# connector.net
KiCad netlist of a schematic drawn in Altium Designer
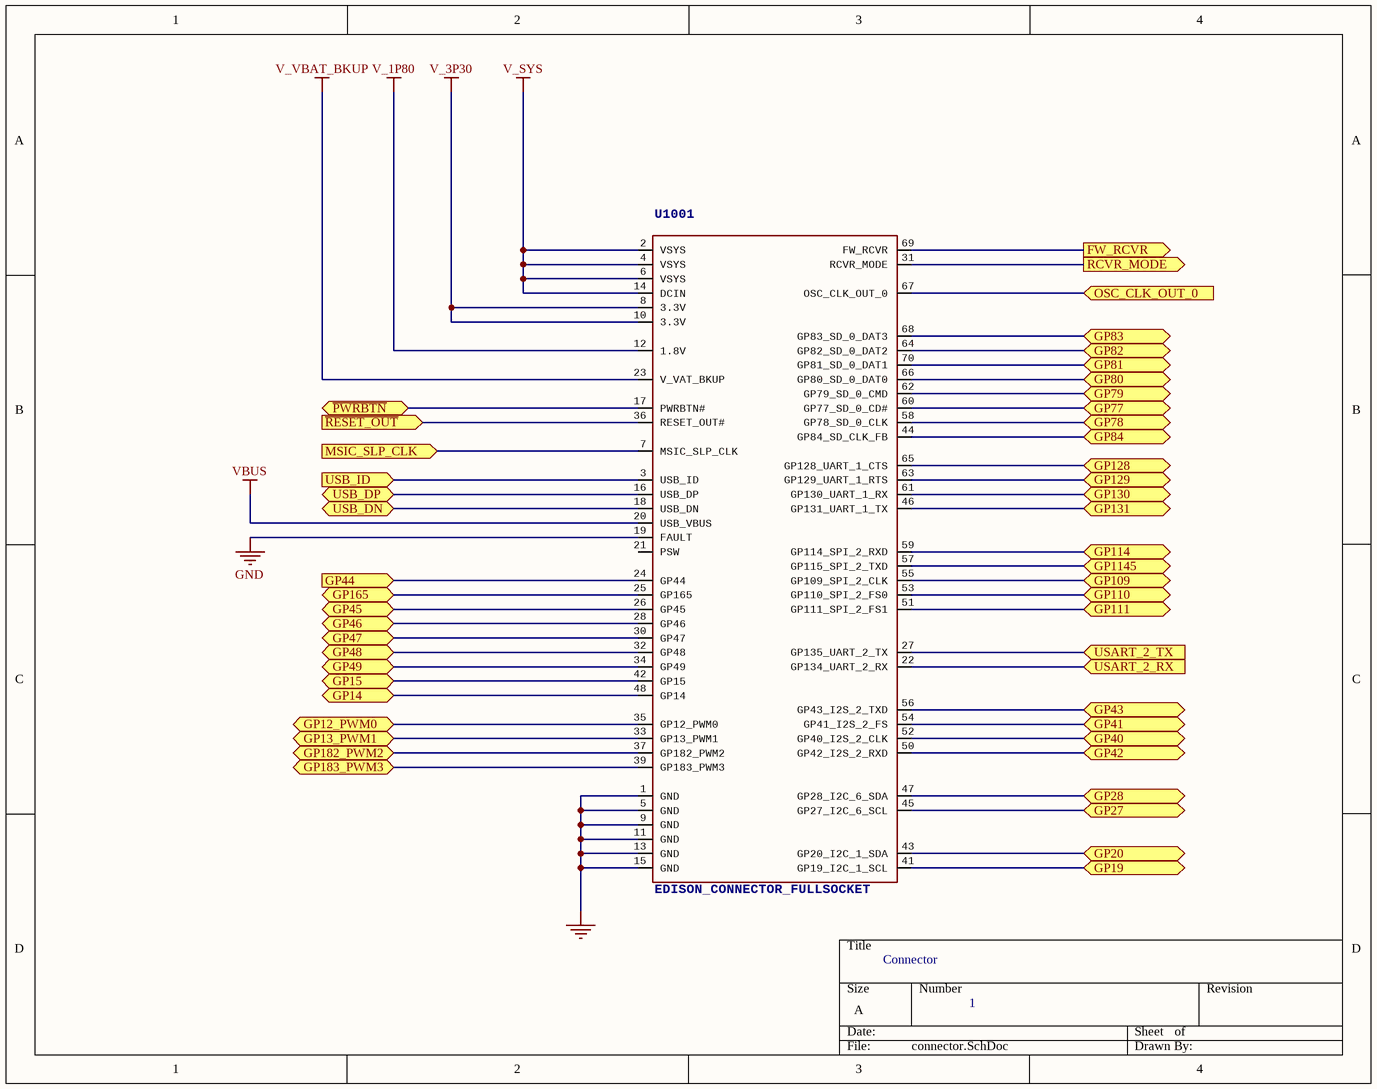
[diagram p0: connector.SchDoc]

(export (version "E")
  (design (tool "Eeschema 10.0.6"))
  (components
    (comp (ref "U1001")
      (value "EDISON_CONNECTOR_FULLSOCKET")
      (footprint "EDISON_DAUGHTER_TOP")
      (libsource (lib "Edison") (part "EDISON_CONNECTOR_FULLSOCKET"))
    )
  )
  (nets
    (net (code "1") (name "/FW_RCVR") (class "Default")
      (node (ref "U1001") (pin "69") (pinfunction "FW_RCVR_69") (pintype "passive"))
    )
    (net (code "2") (name "/GP12_PWM0") (class "Default")
      (node (ref "U1001") (pin "35") (pinfunction "GP12_PWM0_35") (pintype "passive"))
    )
    (net (code "3") (name "/GP13_PWM1") (class "Default")
      (node (ref "U1001") (pin "33") (pinfunction "GP13_PWM1_33") (pintype "passive"))
    )
    (net (code "4") (name "/GP14") (class "Default")
      (node (ref "U1001") (pin "48") (pinfunction "GP14_48") (pintype "passive"))
    )
    (net (code "5") (name "/GP15") (class "Default")
      (node (ref "U1001") (pin "42") (pinfunction "GP15_42") (pintype "passive"))
    )
    (net (code "6") (name "/GP19") (class "Default")
      (node (ref "U1001") (pin "41") (pinfunction "GP19_I2C_1_SCL_41") (pintype "passive"))
    )
    (net (code "7") (name "/GP20") (class "Default")
      (node (ref "U1001") (pin "43") (pinfunction "GP20_I2C_1_SDA_43") (pintype "passive"))
    )
    (net (code "8") (name "/GP27") (class "Default")
      (node (ref "U1001") (pin "45") (pinfunction "GP27_I2C_6_SCL_45") (pintype "passive"))
    )
    (net (code "9") (name "/GP28") (class "Default")
      (node (ref "U1001") (pin "47") (pinfunction "GP28_I2C_6_SDA_47") (pintype "passive"))
    )
    (net (code "10") (name "/GP40") (class "Default")
      (node (ref "U1001") (pin "52") (pinfunction "GP40_I2S_2_CLK_52") (pintype "passive"))
    )
    (net (code "11") (name "/GP41") (class "Default")
      (node (ref "U1001") (pin "54") (pinfunction "GP41_I2S_2_FS_54") (pintype "passive"))
    )
    (net (code "12") (name "/GP42") (class "Default")
      (node (ref "U1001") (pin "50") (pinfunction "GP42_I2S_2_RXD_50") (pintype "passive"))
    )
    (net (code "13") (name "/GP43") (class "Default")
      (node (ref "U1001") (pin "56") (pinfunction "GP43_I2S_2_TXD_56") (pintype "passive"))
    )
    (net (code "14") (name "/GP44") (class "Default")
      (node (ref "U1001") (pin "24") (pinfunction "GP44_24") (pintype "passive"))
    )
    (net (code "15") (name "/GP45") (class "Default")
      (node (ref "U1001") (pin "26") (pinfunction "GP45_26") (pintype "passive"))
    )
    (net (code "16") (name "/GP46") (class "Default")
      (node (ref "U1001") (pin "28") (pinfunction "GP46_28") (pintype "passive"))
    )
    (net (code "17") (name "/GP47") (class "Default")
      (node (ref "U1001") (pin "30") (pinfunction "GP47_30") (pintype "passive"))
    )
    (net (code "18") (name "/GP48") (class "Default")
      (node (ref "U1001") (pin "32") (pinfunction "GP48_32") (pintype "passive"))
    )
    (net (code "19") (name "/GP49") (class "Default")
      (node (ref "U1001") (pin "34") (pinfunction "GP49_34") (pintype "passive"))
    )
    (net (code "20") (name "/GP77") (class "Default")
      (node (ref "U1001") (pin "60") (pinfunction "GP77_SD_0_CD#_60") (pintype "passive"))
    )
    (net (code "21") (name "/GP78") (class "Default")
      (node (ref "U1001") (pin "58") (pinfunction "GP78_SD_0_CLK_58") (pintype "passive"))
    )
    (net (code "22") (name "/GP79") (class "Default")
      (node (ref "U1001") (pin "62") (pinfunction "GP79_SD_0_CMD_62") (pintype "passive"))
    )
    (net (code "23") (name "/GP80") (class "Default")
      (node (ref "U1001") (pin "66") (pinfunction "GP80_SD_0_DAT0_66") (pintype "passive"))
    )
    (net (code "24") (name "/GP81") (class "Default")
      (node (ref "U1001") (pin "70") (pinfunction "GP81_SD_0_DAT1_70") (pintype "passive"))
    )
    (net (code "25") (name "/GP82") (class "Default")
      (node (ref "U1001") (pin "64") (pinfunction "GP82_SD_0_DAT2_64") (pintype "passive"))
    )
    (net (code "26") (name "/GP83") (class "Default")
      (node (ref "U1001") (pin "68") (pinfunction "GP83_SD_0_DAT3_68") (pintype "passive"))
    )
    (net (code "27") (name "/GP84") (class "Default")
      (node (ref "U1001") (pin "44") (pinfunction "GP84_SD_CLK_FB_44") (pintype "passive"))
    )
    (net (code "28") (name "/GP109") (class "Default")
      (node (ref "U1001") (pin "55") (pinfunction "GP109_SPI_2_CLK_55") (pintype "passive"))
    )
    (net (code "29") (name "/GP110") (class "Default")
      (node (ref "U1001") (pin "53") (pinfunction "GP110_SPI_2_FS0_53") (pintype "passive"))
    )
    (net (code "30") (name "/GP111") (class "Default")
      (node (ref "U1001") (pin "51") (pinfunction "GP111_SPI_2_FS1_51") (pintype "passive"))
    )
    (net (code "31") (name "/GP114") (class "Default")
      (node (ref "U1001") (pin "59") (pinfunction "GP114_SPI_2_RXD_59") (pintype "passive"))
    )
    (net (code "32") (name "/GP128") (class "Default")
      (node (ref "U1001") (pin "65") (pinfunction "GP128_UART_1_CTS_65") (pintype "passive"))
    )
    (net (code "33") (name "/GP129") (class "Default")
      (node (ref "U1001") (pin "63") (pinfunction "GP129_UART_1_RTS_63") (pintype "passive"))
    )
    (net (code "34") (name "/GP130") (class "Default")
      (node (ref "U1001") (pin "61") (pinfunction "GP130_UART_1_RX_61") (pintype "passive"))
    )
    (net (code "35") (name "/GP131") (class "Default")
      (node (ref "U1001") (pin "46") (pinfunction "GP131_UART_1_TX_46") (pintype "passive"))
    )
    (net (code "36") (name "/GP165") (class "Default")
      (node (ref "U1001") (pin "25") (pinfunction "GP165_25") (pintype "passive"))
    )
    (net (code "37") (name "/GP182_PWM2") (class "Default")
      (node (ref "U1001") (pin "37") (pinfunction "GP182_PWM2_37") (pintype "passive"))
    )
    (net (code "38") (name "/GP183_PWM3") (class "Default")
      (node (ref "U1001") (pin "39") (pinfunction "GP183_PWM3_39") (pintype "passive"))
    )
    (net (code "39") (name "/GP1145") (class "Default")
      (node (ref "U1001") (pin "57") (pinfunction "GP115_SPI_2_TXD_57") (pintype "passive"))
    )
    (net (code "40") (name "/MSIC_SLP_CLK") (class "Default")
      (node (ref "U1001") (pin "7") (pinfunction "MSIC_SLP_CLK_7") (pintype "passive"))
    )
    (net (code "41") (name "/OSC_CLK_OUT_0") (class "Default")
      (node (ref "U1001") (pin "67") (pinfunction "OSC_CLK_OUT_0_67") (pintype "passive"))
    )
    (net (code "42") (name "/RCVR_MODE") (class "Default")
      (node (ref "U1001") (pin "31") (pinfunction "RCVR_MODE_31") (pintype "passive"))
    )
    (net (code "43") (name "/USART_2_RX") (class "Default")
      (node (ref "U1001") (pin "22") (pinfunction "GP134_UART_2_RX_22") (pintype "passive"))
    )
    (net (code "44") (name "/USART_2_TX") (class "Default")
      (node (ref "U1001") (pin "27") (pinfunction "GP135_UART_2_TX_27") (pintype "passive"))
    )
    (net (code "45") (name "/USB_DN") (class "Default")
      (node (ref "U1001") (pin "18") (pinfunction "USB_DN_18") (pintype "passive"))
    )
    (net (code "46") (name "/USB_DP") (class "Default")
      (node (ref "U1001") (pin "16") (pinfunction "USB_DP_16") (pintype "passive"))
    )
    (net (code "47") (name "/USB_ID") (class "Default")
      (node (ref "U1001") (pin "3") (pinfunction "USB_ID_3") (pintype "passive"))
    )
    (net (code "48") (name "/~{PWRBTN}") (class "Default")
      (node (ref "U1001") (pin "17") (pinfunction "PWRBTN#_17") (pintype "passive"))
    )
    (net (code "49") (name "/~{RESET_OUT}") (class "Default")
      (node (ref "U1001") (pin "36") (pinfunction "RESET_OUT#_36") (pintype "passive"))
    )
    (net (code "50") (name "GND") (class "Default")
      (node (ref "U1001") (pin "1") (pinfunction "GND_1") (pintype "passive"))
      (node (ref "U1001") (pin "11") (pinfunction "GND_11") (pintype "passive"))
      (node (ref "U1001") (pin "13") (pinfunction "GND_13") (pintype "passive"))
      (node (ref "U1001") (pin "15") (pinfunction "GND_15") (pintype "passive"))
      (node (ref "U1001") (pin "19") (pinfunction "FAULT_19") (pintype "passive"))
      (node (ref "U1001") (pin "5") (pinfunction "GND_5") (pintype "passive"))
      (node (ref "U1001") (pin "9") (pinfunction "GND_9") (pintype "passive"))
    )
    (net (code "51") (name "VBUS") (class "Default")
      (node (ref "U1001") (pin "20") (pinfunction "USB_VBUS_20") (pintype "passive"))
    )
    (net (code "52") (name "V_1P80") (class "Default")
      (node (ref "U1001") (pin "12") (pinfunction "1.8V_12") (pintype "passive"))
    )
    (net (code "53") (name "V_3P30") (class "Default")
      (node (ref "U1001") (pin "10") (pinfunction "3.3V_10") (pintype "passive"))
      (node (ref "U1001") (pin "8") (pinfunction "3.3V_8") (pintype "passive"))
    )
    (net (code "54") (name "V_SYS") (class "Default")
      (node (ref "U1001") (pin "14") (pinfunction "DCIN_14") (pintype "passive"))
      (node (ref "U1001") (pin "2") (pinfunction "VSYS_2") (pintype "passive"))
      (node (ref "U1001") (pin "4") (pinfunction "VSYS_4") (pintype "passive"))
      (node (ref "U1001") (pin "6") (pinfunction "VSYS_6") (pintype "passive"))
    )
    (net (code "55") (name "V_VBAT_BKUP") (class "Default")
      (node (ref "U1001") (pin "23") (pinfunction "V_VAT_BKUP_23") (pintype "passive"))
    )
    (net (code "56") (name "unconnected-(U1001-PSW-Pad21)") (class "Default")
      (node (ref "U1001") (pin "21") (pinfunction "PSW_21") (pintype "passive"))
    )
  )
)
